# ProtoShield_V4_0.net
KiCad netlist of a schematic drawn in EAGLE
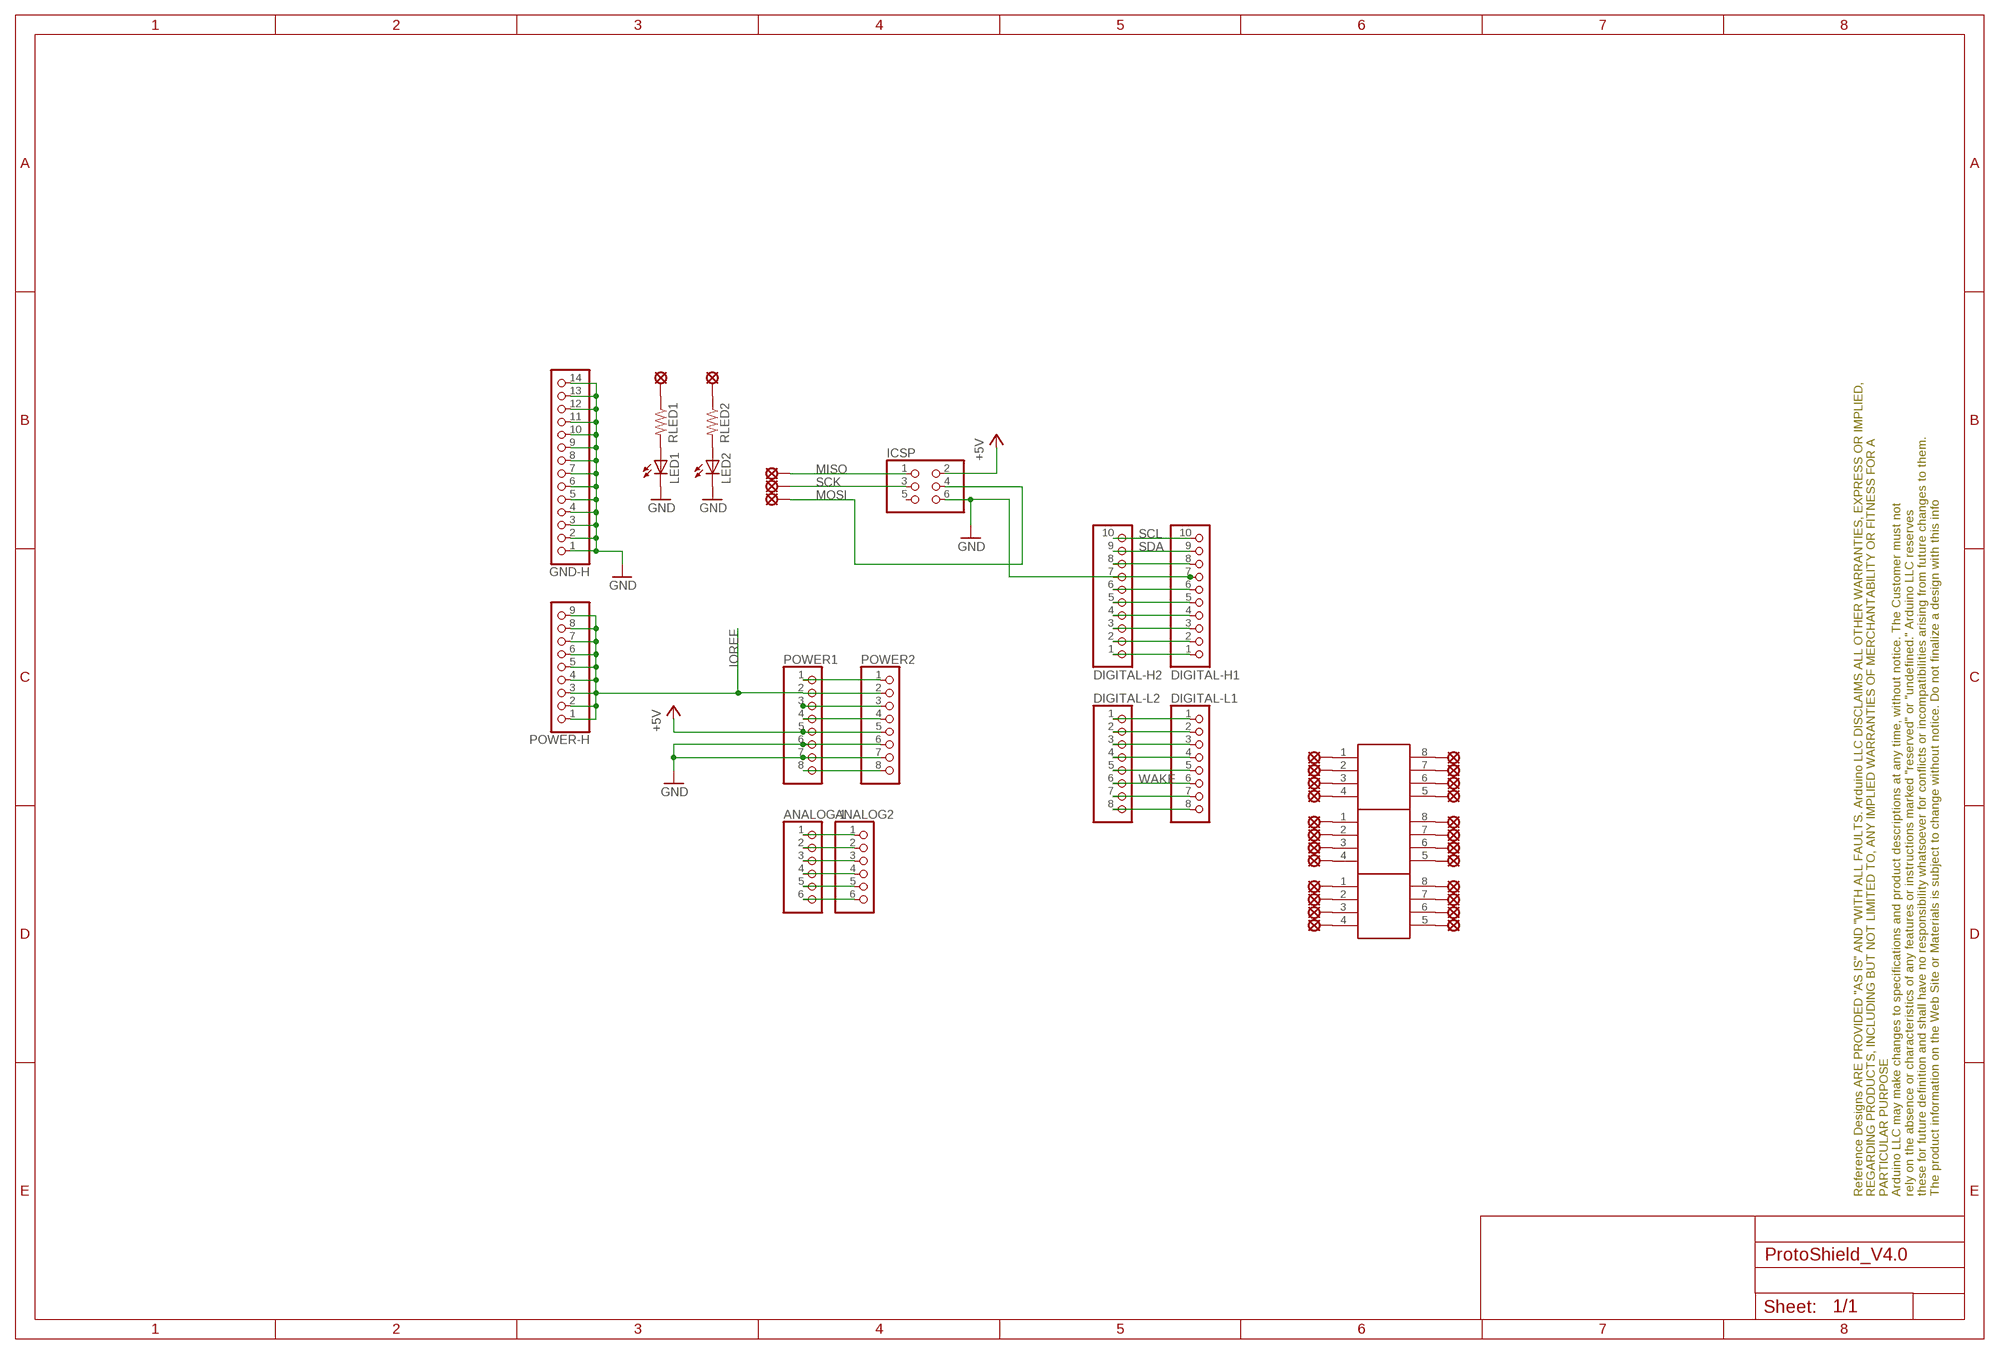
[diagram p0: schematic, sheet 1]

(export (version "E")
  (design (tool "Eeschema 10.0.6"))
  (components
    (comp (ref "ANALOG-1")
      (value "PINHD-1X6")
      (footprint "eagle-import:1X06")
      (libsource (lib "eagle-import") (part "PINHD-1X6"))
    )
    (comp (ref "ANALOG2")
      (value "PINHD-1X6")
      (footprint "eagle-import:1X06")
      (libsource (lib "eagle-import") (part "PINHD-1X6"))
    )
    (comp (ref "DIGITAL-H1")
      (value "PINHD-1X10TH")
      (footprint "eagle-import:1X10-TH")
      (libsource (lib "eagle-import") (part "PINHD-1X10TH"))
    )
    (comp (ref "DIGITAL-H2")
      (value "PINHD-1X10TH")
      (footprint "eagle-import:1X10-TH")
      (libsource (lib "eagle-import") (part "PINHD-1X10TH"))
    )
    (comp (ref "DIGITAL-L1")
      (value "PINHD-1X8")
      (footprint "eagle-import:1X08")
      (fields (field (name "MF") "EPCOS") (field (name "MPN") "B67345B0001X087"))
      (libsource (lib "eagle-import") (part "pinhead_PINHD-1X8"))
    )
    (comp (ref "DIGITAL-L2")
      (value "PINHD-1X8")
      (footprint "eagle-import:1X08")
      (fields (field (name "MF") "EPCOS") (field (name "MPN") "B67345B0001X087"))
      (libsource (lib "eagle-import") (part "pinhead_PINHD-1X8"))
    )
    (comp (ref "FRAME1")
      (value "A3L-LOC")
      (footprint "eagle-import:FRAME")
      (libsource (lib "eagle-import") (part "A3L-LOC"))
    )
    (comp (ref "GND-H")
      (value "PINHD-1X14")
      (footprint "eagle-import:1X14")
      (fields (field (name "MF") "AVX") (field (name "MPN") "08051C472KAZ2A"))
      (libsource (lib "eagle-import") (part "PINHD-1X14"))
    )
    (comp (ref "IC1")
      (value "SMD-8")
      (footprint "eagle-import:SO-8")
      (fields (field (name "MF") "VISHAY BC COMPONENTS") (field (name "MPN") "MAL215374221E3"))
      (libsource (lib "eagle-import") (part "SMD-8"))
    )
    (comp (ref "IC2")
      (value "SMD-8")
      (footprint "eagle-import:SO-8")
      (fields (field (name "MF") "VISHAY BC COMPONENTS") (field (name "MPN") "MAL215374221E3"))
      (libsource (lib "eagle-import") (part "SMD-8"))
    )
    (comp (ref "IC3")
      (value "SMD-8")
      (footprint "eagle-import:SO-8")
      (fields (field (name "MF") "VISHAY BC COMPONENTS") (field (name "MPN") "MAL215374221E3"))
      (libsource (lib "eagle-import") (part "SMD-8"))
    )
    (comp (ref "ICSP")
      (value "PINHD-2X3")
      (footprint "eagle-import:2X03")
      (fields (field (name "MF") "CYNERGY3") (field (name "MPN") "SSF22X035"))
      (libsource (lib "eagle-import") (part "PINHD-2X3"))
    )
    (comp (ref "LED1")
      (value "LED3MM")
      (footprint "eagle-import:LED3MM")
      (fields (field (name "MF") "DIALIGHT") (field (name "MPN") "553-0711F"))
      (libsource (lib "eagle-import") (part "LED3MM"))
    )
    (comp (ref "LED2")
      (value "LED3MM")
      (footprint "eagle-import:LED3MM")
      (fields (field (name "MF") "DIALIGHT") (field (name "MPN") "553-0711F"))
      (libsource (lib "eagle-import") (part "LED3MM"))
    )
    (comp (ref "MISO")
      (value "LSP10")
      (footprint "eagle-import:LSP10")
      (fields (field (name "MF") "RICHCO") (field (name "MPN") "MDLSP1-04M-01"))
      (libsource (lib "eagle-import") (part "LSP10"))
    )
    (comp (ref "MOSI")
      (value "LSP10")
      (footprint "eagle-import:LSP10")
      (fields (field (name "MF") "RICHCO") (field (name "MPN") "MDLSP1-04M-01"))
      (libsource (lib "eagle-import") (part "LSP10"))
    )
    (comp (ref "P1")
      (value "LSP10")
      (footprint "eagle-import:LSP10")
      (fields (field (name "MF") "RICHCO") (field (name "MPN") "MDLSP1-04M-01"))
      (libsource (lib "eagle-import") (part "LSP10"))
    )
    (comp (ref "P2")
      (value "LSP10")
      (footprint "eagle-import:LSP10")
      (fields (field (name "MF") "RICHCO") (field (name "MPN") "MDLSP1-04M-01"))
      (libsource (lib "eagle-import") (part "LSP10"))
    )
    (comp (ref "P3")
      (value "LSP10")
      (footprint "eagle-import:LSP10")
      (fields (field (name "MF") "RICHCO") (field (name "MPN") "MDLSP1-04M-01"))
      (libsource (lib "eagle-import") (part "LSP10"))
    )
    (comp (ref "P4")
      (value "LSP10")
      (footprint "eagle-import:LSP10")
      (fields (field (name "MF") "RICHCO") (field (name "MPN") "MDLSP1-04M-01"))
      (libsource (lib "eagle-import") (part "LSP10"))
    )
    (comp (ref "P5")
      (value "LSP10")
      (footprint "eagle-import:LSP10")
      (fields (field (name "MF") "RICHCO") (field (name "MPN") "MDLSP1-04M-01"))
      (libsource (lib "eagle-import") (part "LSP10"))
    )
    (comp (ref "P6")
      (value "LSP10")
      (footprint "eagle-import:LSP10")
      (fields (field (name "MF") "RICHCO") (field (name "MPN") "MDLSP1-04M-01"))
      (libsource (lib "eagle-import") (part "LSP10"))
    )
    (comp (ref "P7")
      (value "LSP10")
      (footprint "eagle-import:LSP10")
      (fields (field (name "MF") "RICHCO") (field (name "MPN") "MDLSP1-04M-01"))
      (libsource (lib "eagle-import") (part "LSP10"))
    )
    (comp (ref "P8")
      (value "LSP10")
      (footprint "eagle-import:LSP10")
      (fields (field (name "MF") "RICHCO") (field (name "MPN") "MDLSP1-04M-01"))
      (libsource (lib "eagle-import") (part "LSP10"))
    )
    (comp (ref "P9")
      (value "LSP10")
      (footprint "eagle-import:LSP10")
      (fields (field (name "MF") "RICHCO") (field (name "MPN") "MDLSP1-04M-01"))
      (libsource (lib "eagle-import") (part "LSP10"))
    )
    (comp (ref "P10")
      (value "LSP10")
      (footprint "eagle-import:LSP10")
      (fields (field (name "MF") "RICHCO") (field (name "MPN") "MDLSP1-04M-01"))
      (libsource (lib "eagle-import") (part "LSP10"))
    )
    (comp (ref "P11")
      (value "LSP10")
      (footprint "eagle-import:LSP10")
      (fields (field (name "MF") "RICHCO") (field (name "MPN") "MDLSP1-04M-01"))
      (libsource (lib "eagle-import") (part "LSP10"))
    )
    (comp (ref "P12")
      (value "LSP10")
      (footprint "eagle-import:LSP10")
      (fields (field (name "MF") "RICHCO") (field (name "MPN") "MDLSP1-04M-01"))
      (libsource (lib "eagle-import") (part "LSP10"))
    )
    (comp (ref "P13")
      (value "LSP10")
      (footprint "eagle-import:LSP10")
      (fields (field (name "MF") "RICHCO") (field (name "MPN") "MDLSP1-04M-01"))
      (libsource (lib "eagle-import") (part "LSP10"))
    )
    (comp (ref "P14")
      (value "LSP10")
      (footprint "eagle-import:LSP10")
      (fields (field (name "MF") "RICHCO") (field (name "MPN") "MDLSP1-04M-01"))
      (libsource (lib "eagle-import") (part "LSP10"))
    )
    (comp (ref "P15")
      (value "LSP10")
      (footprint "eagle-import:LSP10")
      (fields (field (name "MF") "RICHCO") (field (name "MPN") "MDLSP1-04M-01"))
      (libsource (lib "eagle-import") (part "LSP10"))
    )
    (comp (ref "P16")
      (value "LSP10")
      (footprint "eagle-import:LSP10")
      (fields (field (name "MF") "RICHCO") (field (name "MPN") "MDLSP1-04M-01"))
      (libsource (lib "eagle-import") (part "LSP10"))
    )
    (comp (ref "P17")
      (value "LSP10")
      (footprint "eagle-import:LSP10")
      (fields (field (name "MF") "RICHCO") (field (name "MPN") "MDLSP1-04M-01"))
      (libsource (lib "eagle-import") (part "LSP10"))
    )
    (comp (ref "P18")
      (value "LSP10")
      (footprint "eagle-import:LSP10")
      (fields (field (name "MF") "RICHCO") (field (name "MPN") "MDLSP1-04M-01"))
      (libsource (lib "eagle-import") (part "LSP10"))
    )
    (comp (ref "P19")
      (value "LSP10")
      (footprint "eagle-import:LSP10")
      (fields (field (name "MF") "RICHCO") (field (name "MPN") "MDLSP1-04M-01"))
      (libsource (lib "eagle-import") (part "LSP10"))
    )
    (comp (ref "P20")
      (value "LSP10")
      (footprint "eagle-import:LSP10")
      (fields (field (name "MF") "RICHCO") (field (name "MPN") "MDLSP1-04M-01"))
      (libsource (lib "eagle-import") (part "LSP10"))
    )
    (comp (ref "P21")
      (value "LSP10")
      (footprint "eagle-import:LSP10")
      (fields (field (name "MF") "RICHCO") (field (name "MPN") "MDLSP1-04M-01"))
      (libsource (lib "eagle-import") (part "LSP10"))
    )
    (comp (ref "P22")
      (value "LSP10")
      (footprint "eagle-import:LSP10")
      (fields (field (name "MF") "RICHCO") (field (name "MPN") "MDLSP1-04M-01"))
      (libsource (lib "eagle-import") (part "LSP10"))
    )
    (comp (ref "P23")
      (value "LSP10")
      (footprint "eagle-import:LSP10")
      (fields (field (name "MF") "RICHCO") (field (name "MPN") "MDLSP1-04M-01"))
      (libsource (lib "eagle-import") (part "LSP10"))
    )
    (comp (ref "P24")
      (value "LSP10")
      (footprint "eagle-import:LSP10")
      (fields (field (name "MF") "RICHCO") (field (name "MPN") "MDLSP1-04M-01"))
      (libsource (lib "eagle-import") (part "LSP10"))
    )
    (comp (ref "PLED1")
      (value "LSP10")
      (footprint "eagle-import:LSP10")
      (fields (field (name "MF") "RICHCO") (field (name "MPN") "MDLSP1-04M-01"))
      (libsource (lib "eagle-import") (part "LSP10"))
    )
    (comp (ref "PLED2")
      (value "LSP10")
      (footprint "eagle-import:LSP10")
      (fields (field (name "MF") "RICHCO") (field (name "MPN") "MDLSP1-04M-01"))
      (libsource (lib "eagle-import") (part "LSP10"))
    )
    (comp (ref "POWER-H")
      (value "PINHD-1X9")
      (footprint "eagle-import:1X9")
      (fields (field (name "MF") "CML INNOVATIVE TECHNOLOGIES") (field (name "MPN") "513LF"))
      (libsource (lib "eagle-import") (part "PINHD-1X9"))
    )
    (comp (ref "POWER1")
      (value "PINHD-1X8TH")
      (footprint "eagle-import:1X08-TH")
      (libsource (lib "eagle-import") (part "PINHD-1X8TH"))
    )
    (comp (ref "POWER2")
      (value "PINHD-1X8TH")
      (footprint "eagle-import:1X08-TH")
      (libsource (lib "eagle-import") (part "PINHD-1X8TH"))
    )
    (comp (ref "RLED1")
      (value "6MM.3")
      (footprint "eagle-import:R0207_3")
      (libsource (lib "eagle-import") (part "6MM.3"))
    )
    (comp (ref "RLED2")
      (value "6MM.3")
      (footprint "eagle-import:R0207_3")
      (libsource (lib "eagle-import") (part "6MM.3"))
    )
    (comp (ref "SCK")
      (value "LSP10")
      (footprint "eagle-import:LSP10")
      (fields (field (name "MF") "RICHCO") (field (name "MPN") "MDLSP1-04M-01"))
      (libsource (lib "eagle-import") (part "LSP10"))
    )
  )
  (nets
    (net (code "1") (name "+5V") (class "Default")
      (node (ref "ICSP") (pin "2") (pinfunction "2_2") (pintype "passive"))
      (node (ref "POWER1") (pin "5") (pinfunction "5_5") (pintype "passive"))
      (node (ref "POWER2") (pin "5") (pinfunction "5_5") (pintype "passive"))
    )
    (net (code "2") (name "/IOREF") (class "Default")
      (node (ref "POWER-H") (pin "1") (pinfunction "1_1") (pintype "passive"))
      (node (ref "POWER-H") (pin "2") (pinfunction "2_2") (pintype "passive"))
      (node (ref "POWER-H") (pin "3") (pinfunction "3_3") (pintype "passive"))
      (node (ref "POWER-H") (pin "4") (pinfunction "4_4") (pintype "passive"))
      (node (ref "POWER-H") (pin "5") (pinfunction "5_5") (pintype "passive"))
      (node (ref "POWER-H") (pin "6") (pinfunction "6_6") (pintype "passive"))
      (node (ref "POWER-H") (pin "7") (pinfunction "7_7") (pintype "passive"))
      (node (ref "POWER-H") (pin "8") (pinfunction "8_8") (pintype "passive"))
      (node (ref "POWER-H") (pin "9") (pinfunction "9_9") (pintype "passive"))
      (node (ref "POWER1") (pin "2") (pinfunction "2_2") (pintype "passive"))
      (node (ref "POWER2") (pin "2") (pinfunction "2_2") (pintype "passive"))
    )
    (net (code "3") (name "/MISO") (class "Default")
      (node (ref "ICSP") (pin "1") (pinfunction "1_1") (pintype "passive"))
      (node (ref "MISO") (pin "MP") (pinfunction "MP_MP") (pintype "passive"))
    )
    (net (code "4") (name "/MOSI") (class "Default")
      (node (ref "ICSP") (pin "4") (pinfunction "4_4") (pintype "passive"))
      (node (ref "MOSI") (pin "MP") (pinfunction "MP_MP") (pintype "passive"))
    )
    (net (code "5") (name "/SCK") (class "Default")
      (node (ref "ICSP") (pin "3") (pinfunction "3_3") (pintype "passive"))
      (node (ref "SCK") (pin "MP") (pinfunction "MP_MP") (pintype "passive"))
    )
    (net (code "6") (name "/SCL") (class "Default")
      (node (ref "DIGITAL-H1") (pin "10") (pinfunction "10_10") (pintype "passive"))
      (node (ref "DIGITAL-H2") (pin "10") (pinfunction "10_10") (pintype "passive"))
    )
    (net (code "7") (name "/SDA") (class "Default")
      (node (ref "DIGITAL-H1") (pin "9") (pinfunction "9_9") (pintype "passive"))
      (node (ref "DIGITAL-H2") (pin "9") (pinfunction "9_9") (pintype "passive"))
    )
    (net (code "8") (name "/WAKE") (class "Default")
      (node (ref "DIGITAL-L1") (pin "6") (pinfunction "6_6") (pintype "passive"))
      (node (ref "DIGITAL-L2") (pin "6") (pinfunction "6_6") (pintype "passive"))
    )
    (net (code "9") (name "GND") (class "Default")
      (node (ref "DIGITAL-H1") (pin "7") (pinfunction "7_7") (pintype "passive"))
      (node (ref "DIGITAL-H2") (pin "7") (pinfunction "7_7") (pintype "passive"))
      (node (ref "GND-H") (pin "1") (pinfunction "1_1") (pintype "passive"))
      (node (ref "GND-H") (pin "10") (pinfunction "10_10") (pintype "passive"))
      (node (ref "GND-H") (pin "11") (pinfunction "11_11") (pintype "passive"))
      (node (ref "GND-H") (pin "12") (pinfunction "12_12") (pintype "passive"))
      (node (ref "GND-H") (pin "13") (pinfunction "13_13") (pintype "passive"))
      (node (ref "GND-H") (pin "14") (pinfunction "14_14") (pintype "passive"))
      (node (ref "GND-H") (pin "2") (pinfunction "2_2") (pintype "passive"))
      (node (ref "GND-H") (pin "3") (pinfunction "3_3") (pintype "passive"))
      (node (ref "GND-H") (pin "4") (pinfunction "4_4") (pintype "passive"))
      (node (ref "GND-H") (pin "5") (pinfunction "5_5") (pintype "passive"))
      (node (ref "GND-H") (pin "6") (pinfunction "6_6") (pintype "passive"))
      (node (ref "GND-H") (pin "7") (pinfunction "7_7") (pintype "passive"))
      (node (ref "GND-H") (pin "8") (pinfunction "8_8") (pintype "passive"))
      (node (ref "GND-H") (pin "9") (pinfunction "9_9") (pintype "passive"))
      (node (ref "ICSP") (pin "6") (pinfunction "6_6") (pintype "passive"))
      (node (ref "LED1") (pin "K") (pinfunction "C_K") (pintype "passive"))
      (node (ref "LED2") (pin "K") (pinfunction "C_K") (pintype "passive"))
      (node (ref "POWER1") (pin "7") (pinfunction "7_7") (pintype "passive"))
      (node (ref "POWER2") (pin "7") (pinfunction "7_7") (pintype "passive"))
    )
    (net (code "10") (name "Net-(ANALOG-1-Pad1)") (class "Default")
      (node (ref "ANALOG-1") (pin "1") (pinfunction "1_1") (pintype "passive"))
      (node (ref "ANALOG2") (pin "1") (pinfunction "1_1") (pintype "passive"))
    )
    (net (code "11") (name "Net-(ANALOG-1-Pad2)") (class "Default")
      (node (ref "ANALOG-1") (pin "2") (pinfunction "2_2") (pintype "passive"))
      (node (ref "ANALOG2") (pin "2") (pinfunction "2_2") (pintype "passive"))
    )
    (net (code "12") (name "Net-(ANALOG-1-Pad3)") (class "Default")
      (node (ref "ANALOG-1") (pin "3") (pinfunction "3_3") (pintype "passive"))
      (node (ref "ANALOG2") (pin "3") (pinfunction "3_3") (pintype "passive"))
    )
    (net (code "13") (name "Net-(ANALOG-1-Pad4)") (class "Default")
      (node (ref "ANALOG-1") (pin "4") (pinfunction "4_4") (pintype "passive"))
      (node (ref "ANALOG2") (pin "4") (pinfunction "4_4") (pintype "passive"))
    )
    (net (code "14") (name "Net-(ANALOG-1-Pad5)") (class "Default")
      (node (ref "ANALOG-1") (pin "5") (pinfunction "5_5") (pintype "passive"))
      (node (ref "ANALOG2") (pin "5") (pinfunction "5_5") (pintype "passive"))
    )
    (net (code "15") (name "Net-(ANALOG-1-Pad6)") (class "Default")
      (node (ref "ANALOG-1") (pin "6") (pinfunction "6_6") (pintype "passive"))
      (node (ref "ANALOG2") (pin "6") (pinfunction "6_6") (pintype "passive"))
    )
    (net (code "16") (name "Net-(DIGITAL-H1-Pad1)") (class "Default")
      (node (ref "DIGITAL-H1") (pin "1") (pinfunction "1_1") (pintype "passive"))
      (node (ref "DIGITAL-H2") (pin "1") (pinfunction "1_1") (pintype "passive"))
    )
    (net (code "17") (name "Net-(DIGITAL-H1-Pad2)") (class "Default")
      (node (ref "DIGITAL-H1") (pin "2") (pinfunction "2_2") (pintype "passive"))
      (node (ref "DIGITAL-H2") (pin "2") (pinfunction "2_2") (pintype "passive"))
    )
    (net (code "18") (name "Net-(DIGITAL-H1-Pad3)") (class "Default")
      (node (ref "DIGITAL-H1") (pin "3") (pinfunction "3_3") (pintype "passive"))
      (node (ref "DIGITAL-H2") (pin "3") (pinfunction "3_3") (pintype "passive"))
    )
    (net (code "19") (name "Net-(DIGITAL-H1-Pad4)") (class "Default")
      (node (ref "DIGITAL-H1") (pin "4") (pinfunction "4_4") (pintype "passive"))
      (node (ref "DIGITAL-H2") (pin "4") (pinfunction "4_4") (pintype "passive"))
    )
    (net (code "20") (name "Net-(DIGITAL-H1-Pad5)") (class "Default")
      (node (ref "DIGITAL-H1") (pin "5") (pinfunction "5_5") (pintype "passive"))
      (node (ref "DIGITAL-H2") (pin "5") (pinfunction "5_5") (pintype "passive"))
    )
    (net (code "21") (name "Net-(DIGITAL-H1-Pad6)") (class "Default")
      (node (ref "DIGITAL-H1") (pin "6") (pinfunction "6_6") (pintype "passive"))
      (node (ref "DIGITAL-H2") (pin "6") (pinfunction "6_6") (pintype "passive"))
    )
    (net (code "22") (name "Net-(DIGITAL-H1-Pad8)") (class "Default")
      (node (ref "DIGITAL-H1") (pin "8") (pinfunction "8_8") (pintype "passive"))
      (node (ref "DIGITAL-H2") (pin "8") (pinfunction "8_8") (pintype "passive"))
    )
    (net (code "23") (name "Net-(DIGITAL-L1-Pad1)") (class "Default")
      (node (ref "DIGITAL-L1") (pin "1") (pinfunction "1_1") (pintype "passive"))
      (node (ref "DIGITAL-L2") (pin "1") (pinfunction "1_1") (pintype "passive"))
    )
    (net (code "24") (name "Net-(DIGITAL-L1-Pad2)") (class "Default")
      (node (ref "DIGITAL-L1") (pin "2") (pinfunction "2_2") (pintype "passive"))
      (node (ref "DIGITAL-L2") (pin "2") (pinfunction "2_2") (pintype "passive"))
    )
    (net (code "25") (name "Net-(DIGITAL-L1-Pad3)") (class "Default")
      (node (ref "DIGITAL-L1") (pin "3") (pinfunction "3_3") (pintype "passive"))
      (node (ref "DIGITAL-L2") (pin "3") (pinfunction "3_3") (pintype "passive"))
    )
    (net (code "26") (name "Net-(DIGITAL-L1-Pad4)") (class "Default")
      (node (ref "DIGITAL-L1") (pin "4") (pinfunction "4_4") (pintype "passive"))
      (node (ref "DIGITAL-L2") (pin "4") (pinfunction "4_4") (pintype "passive"))
    )
    (net (code "27") (name "Net-(DIGITAL-L1-Pad5)") (class "Default")
      (node (ref "DIGITAL-L1") (pin "5") (pinfunction "5_5") (pintype "passive"))
      (node (ref "DIGITAL-L2") (pin "5") (pinfunction "5_5") (pintype "passive"))
    )
    (net (code "28") (name "Net-(DIGITAL-L1-Pad7)") (class "Default")
      (node (ref "DIGITAL-L1") (pin "7") (pinfunction "7_7") (pintype "passive"))
      (node (ref "DIGITAL-L2") (pin "7") (pinfunction "7_7") (pintype "passive"))
    )
    (net (code "29") (name "Net-(DIGITAL-L1-Pad8)") (class "Default")
      (node (ref "DIGITAL-L1") (pin "8") (pinfunction "8_8") (pintype "passive"))
      (node (ref "DIGITAL-L2") (pin "8") (pinfunction "8_8") (pintype "passive"))
    )
    (net (code "30") (name "Net-(IC1-Pad1)") (class "Default")
      (node (ref "IC1") (pin "1") (pinfunction "1_1") (pintype "bidirectional"))
      (node (ref "P1") (pin "MP") (pinfunction "MP_MP") (pintype "passive"))
    )
    (net (code "31") (name "Net-(IC1-Pad2)") (class "Default")
      (node (ref "IC1") (pin "2") (pinfunction "2_2") (pintype "bidirectional"))
      (node (ref "P2") (pin "MP") (pinfunction "MP_MP") (pintype "passive"))
    )
    (net (code "32") (name "Net-(IC1-Pad3)") (class "Default")
      (node (ref "IC1") (pin "3") (pinfunction "3_3") (pintype "bidirectional"))
      (node (ref "P3") (pin "MP") (pinfunction "MP_MP") (pintype "passive"))
    )
    (net (code "33") (name "Net-(IC1-Pad4)") (class "Default")
      (node (ref "IC1") (pin "4") (pinfunction "4_4") (pintype "bidirectional"))
      (node (ref "P4") (pin "MP") (pinfunction "MP_MP") (pintype "passive"))
    )
    (net (code "34") (name "Net-(IC1-Pad5)") (class "Default")
      (node (ref "IC1") (pin "5") (pinfunction "5_5") (pintype "bidirectional"))
      (node (ref "P21") (pin "MP") (pinfunction "MP_MP") (pintype "passive"))
    )
    (net (code "35") (name "Net-(IC1-Pad6)") (class "Default")
      (node (ref "IC1") (pin "6") (pinfunction "6_6") (pintype "bidirectional"))
      (node (ref "P22") (pin "MP") (pinfunction "MP_MP") (pintype "passive"))
    )
    (net (code "36") (name "Net-(IC1-Pad7)") (class "Default")
      (node (ref "IC1") (pin "7") (pinfunction "7_7") (pintype "bidirectional"))
      (node (ref "P23") (pin "MP") (pinfunction "MP_MP") (pintype "passive"))
    )
    (net (code "37") (name "Net-(IC1-Pad8)") (class "Default")
      (node (ref "IC1") (pin "8") (pinfunction "8_8") (pintype "bidirectional"))
      (node (ref "P24") (pin "MP") (pinfunction "MP_MP") (pintype "passive"))
    )
    (net (code "38") (name "Net-(IC2-Pad1)") (class "Default")
      (node (ref "IC2") (pin "1") (pinfunction "1_1") (pintype "bidirectional"))
      (node (ref "P5") (pin "MP") (pinfunction "MP_MP") (pintype "passive"))
    )
    (net (code "39") (name "Net-(IC2-Pad2)") (class "Default")
      (node (ref "IC2") (pin "2") (pinfunction "2_2") (pintype "bidirectional"))
      (node (ref "P6") (pin "MP") (pinfunction "MP_MP") (pintype "passive"))
    )
    (net (code "40") (name "Net-(IC2-Pad3)") (class "Default")
      (node (ref "IC2") (pin "3") (pinfunction "3_3") (pintype "bidirectional"))
      (node (ref "P7") (pin "MP") (pinfunction "MP_MP") (pintype "passive"))
    )
    (net (code "41") (name "Net-(IC2-Pad4)") (class "Default")
      (node (ref "IC2") (pin "4") (pinfunction "4_4") (pintype "bidirectional"))
      (node (ref "P8") (pin "MP") (pinfunction "MP_MP") (pintype "passive"))
    )
    (net (code "42") (name "Net-(IC2-Pad5)") (class "Default")
      (node (ref "IC2") (pin "5") (pinfunction "5_5") (pintype "bidirectional"))
      (node (ref "P17") (pin "MP") (pinfunction "MP_MP") (pintype "passive"))
    )
    (net (code "43") (name "Net-(IC2-Pad6)") (class "Default")
      (node (ref "IC2") (pin "6") (pinfunction "6_6") (pintype "bidirectional"))
      (node (ref "P18") (pin "MP") (pinfunction "MP_MP") (pintype "passive"))
    )
    (net (code "44") (name "Net-(IC2-Pad7)") (class "Default")
      (node (ref "IC2") (pin "7") (pinfunction "7_7") (pintype "bidirectional"))
      (node (ref "P19") (pin "MP") (pinfunction "MP_MP") (pintype "passive"))
    )
    (net (code "45") (name "Net-(IC2-Pad8)") (class "Default")
      (node (ref "IC2") (pin "8") (pinfunction "8_8") (pintype "bidirectional"))
      (node (ref "P20") (pin "MP") (pinfunction "MP_MP") (pintype "passive"))
    )
    (net (code "46") (name "Net-(IC3-Pad1)") (class "Default")
      (node (ref "IC3") (pin "1") (pinfunction "1_1") (pintype "bidirectional"))
      (node (ref "P9") (pin "MP") (pinfunction "MP_MP") (pintype "passive"))
    )
    (net (code "47") (name "Net-(IC3-Pad2)") (class "Default")
      (node (ref "IC3") (pin "2") (pinfunction "2_2") (pintype "bidirectional"))
      (node (ref "P10") (pin "MP") (pinfunction "MP_MP") (pintype "passive"))
    )
    (net (code "48") (name "Net-(IC3-Pad3)") (class "Default")
      (node (ref "IC3") (pin "3") (pinfunction "3_3") (pintype "bidirectional"))
      (node (ref "P11") (pin "MP") (pinfunction "MP_MP") (pintype "passive"))
    )
    (net (code "49") (name "Net-(IC3-Pad4)") (class "Default")
      (node (ref "IC3") (pin "4") (pinfunction "4_4") (pintype "bidirectional"))
      (node (ref "P12") (pin "MP") (pinfunction "MP_MP") (pintype "passive"))
    )
    (net (code "50") (name "Net-(IC3-Pad5)") (class "Default")
      (node (ref "IC3") (pin "5") (pinfunction "5_5") (pintype "bidirectional"))
      (node (ref "P13") (pin "MP") (pinfunction "MP_MP") (pintype "passive"))
    )
    (net (code "51") (name "Net-(IC3-Pad6)") (class "Default")
      (node (ref "IC3") (pin "6") (pinfunction "6_6") (pintype "bidirectional"))
      (node (ref "P14") (pin "MP") (pinfunction "MP_MP") (pintype "passive"))
    )
    (net (code "52") (name "Net-(IC3-Pad7)") (class "Default")
      (node (ref "IC3") (pin "7") (pinfunction "7_7") (pintype "bidirectional"))
      (node (ref "P15") (pin "MP") (pinfunction "MP_MP") (pintype "passive"))
    )
    (net (code "53") (name "Net-(IC3-Pad8)") (class "Default")
      (node (ref "IC3") (pin "8") (pinfunction "8_8") (pintype "bidirectional"))
      (node (ref "P16") (pin "MP") (pinfunction "MP_MP") (pintype "passive"))
    )
    (net (code "54") (name "Net-(LED1-PadA)") (class "Default")
      (node (ref "LED1") (pin "A") (pinfunction "A_A") (pintype "passive"))
      (node (ref "RLED1") (pin "2") (pinfunction "2_2") (pintype "passive"))
    )
    (net (code "55") (name "Net-(LED2-PadA)") (class "Default")
      (node (ref "LED2") (pin "A") (pinfunction "A_A") (pintype "passive"))
      (node (ref "RLED2") (pin "2") (pinfunction "2_2") (pintype "passive"))
    )
    (net (code "56") (name "Net-(PLED1-PadMP)") (class "Default")
      (node (ref "PLED1") (pin "MP") (pinfunction "MP_MP") (pintype "passive"))
      (node (ref "RLED1") (pin "1") (pinfunction "1_1") (pintype "passive"))
    )
    (net (code "57") (name "Net-(PLED2-PadMP)") (class "Default")
      (node (ref "PLED2") (pin "MP") (pinfunction "MP_MP") (pintype "passive"))
      (node (ref "RLED2") (pin "1") (pinfunction "1_1") (pintype "passive"))
    )
    (net (code "58") (name "Net-(POWER1-Pad1)") (class "Default")
      (node (ref "POWER1") (pin "1") (pinfunction "1_1") (pintype "passive"))
      (node (ref "POWER2") (pin "1") (pinfunction "1_1") (pintype "passive"))
    )
    (net (code "59") (name "Net-(POWER1-Pad3)") (class "Default")
      (node (ref "POWER1") (pin "3") (pinfunction "3_3") (pintype "passive"))
      (node (ref "POWER2") (pin "3") (pinfunction "3_3") (pintype "passive"))
    )
    (net (code "60") (name "Net-(POWER1-Pad4)") (class "Default")
      (node (ref "POWER1") (pin "4") (pinfunction "4_4") (pintype "passive"))
      (node (ref "POWER2") (pin "4") (pinfunction "4_4") (pintype "passive"))
    )
    (net (code "61") (name "Net-(POWER1-Pad6)") (class "Default")
      (node (ref "POWER1") (pin "6") (pinfunction "6_6") (pintype "passive"))
      (node (ref "POWER2") (pin "6") (pinfunction "6_6") (pintype "passive"))
    )
    (net (code "62") (name "Net-(POWER1-Pad8)") (class "Default")
      (node (ref "POWER1") (pin "8") (pinfunction "8_8") (pintype "passive"))
      (node (ref "POWER2") (pin "8") (pinfunction "8_8") (pintype "passive"))
    )
    (net (code "63") (name "unconnected-(ICSP-Pad5)") (class "Default")
      (node (ref "ICSP") (pin "5") (pinfunction "5_5") (pintype "passive"))
    )
  )
)
